# PAYL0001_GMSK.net
KiCad netlist of a schematic drawn in Altium Designer
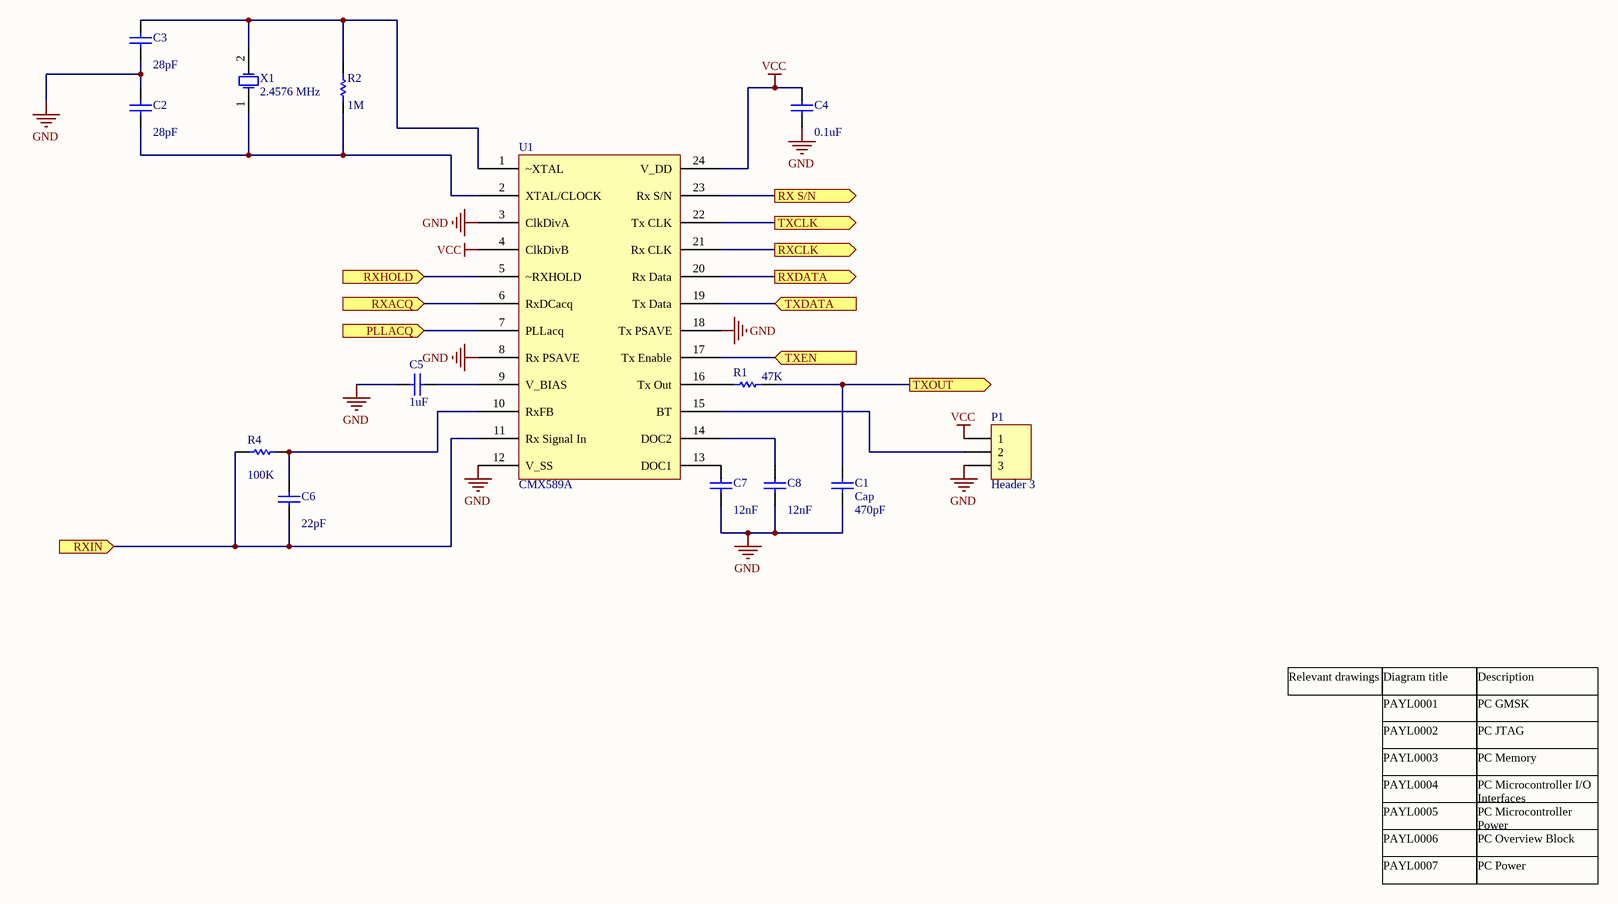
[diagram p0: PAYL0001_GMSK.SchDoc]

(export (version "E")
  (design (tool "Eeschema 10.0.6"))
  (components
    (comp (ref "C1")
      (value "Cap")
      (footprint "C0805")
      (description "Capacitor")
      (fields (field (name "ALTIUM_VALUE") "470pF") (field (name "PUBLISHER") "Altium Limited"))
      (libsource (lib "Miscellaneous Devices") (part "Cap"))
    )
    (comp (ref "C2")
      (value "28pF")
      (footprint "C0805")
      (description "Capacitor")
      (fields (field (name "Comment") "Cap") (field (name "PUBLISHER") "Altium Limited"))
      (libsource (lib "Miscellaneous Devices") (part "Cap"))
    )
    (comp (ref "C3")
      (value "28pF")
      (footprint "C0805")
      (description "Capacitor")
      (fields (field (name "Comment") "Cap") (field (name "PUBLISHER") "Altium Limited"))
      (libsource (lib "Miscellaneous Devices") (part "Cap"))
    )
    (comp (ref "C4")
      (value "0.1uF")
      (footprint "C0805")
      (description "Capacitor")
      (fields (field (name "Comment") "Cap") (field (name "PUBLISHER") "Altium Limited"))
      (libsource (lib "Miscellaneous Devices") (part "Cap"))
    )
    (comp (ref "C5")
      (value "1uF")
      (footprint "C0805")
      (description "Capacitor")
      (fields (field (name "Comment") "Cap") (field (name "PUBLISHER") "Altium Limited"))
      (libsource (lib "Miscellaneous Devices") (part "Cap"))
    )
    (comp (ref "C6")
      (value "22pF")
      (footprint "C0805")
      (description "Capacitor")
      (fields (field (name "Comment") "Cap") (field (name "PUBLISHER") "Altium Limited"))
      (libsource (lib "Miscellaneous Devices") (part "Cap"))
    )
    (comp (ref "C7")
      (value "12nF")
      (footprint "C0805")
      (description "Capacitor")
      (fields (field (name "Comment") "Cap") (field (name "PUBLISHER") "Altium Limited"))
      (libsource (lib "Miscellaneous Devices") (part "Cap"))
    )
    (comp (ref "C8")
      (value "12nF")
      (footprint "C0805")
      (description "Capacitor")
      (fields (field (name "Comment") "Cap") (field (name "PUBLISHER") "Altium Limited"))
      (libsource (lib "Miscellaneous Devices") (part "Cap"))
    )
    (comp (ref "P1")
      (value "Header 3")
      (footprint "HDR1X3")
      (description "Header, 3-Pin")
      (fields (field (name "PUBLISHER") "Altium Limited"))
      (libsource (lib "Miscellaneous Connectors") (part "Header 3"))
    )
    (comp (ref "R1")
      (value "47K")
      (footprint "C0805")
      (description "Resistor")
      (fields (field (name "Comment") "Res1") (field (name "PUBLISHER") "Altium Limited"))
      (libsource (lib "Miscellaneous Devices") (part "Res1"))
    )
    (comp (ref "R2")
      (value "1M")
      (footprint "C0805")
      (description "Resistor")
      (fields (field (name "Comment") "Res1") (field (name "PUBLISHER") "Altium Limited"))
      (libsource (lib "Miscellaneous Devices") (part "Res1"))
    )
    (comp (ref "R4")
      (value "100K")
      (footprint "C0805")
      (description "Resistor")
      (fields (field (name "Comment") "Res1") (field (name "PUBLISHER") "Altium Limited"))
      (libsource (lib "Miscellaneous Devices") (part "Res1"))
    )
    (comp (ref "U1") (value "CMX589A") (footprint "CMX589AD2") (libsource (lib "CMX589A") (part "CMX589A")))
    (comp (ref "X1")
      (value "2.4576 MHz")
      (footprint "XTAL")
      (description "Crystal Oscillator")
      (fields (field (name "PUBLISHER") "Altium Limited"))
      (libsource (lib "Miscellaneous Devices") (part "XTAL"))
    )
  )
  (nets
    (net (code "1") (name "/PLLACQ") (class "Default")
      (node (ref "U1") (pin "7") (pinfunction "PLLacq_7") (pintype "passive"))
    )
    (net (code "2") (name "/RX S{slash}N") (class "Default")
      (node (ref "U1") (pin "23") (pinfunction "Rx_S/N_23") (pintype "passive"))
    )
    (net (code "3") (name "/RXACQ") (class "Default")
      (node (ref "U1") (pin "6") (pinfunction "RxDCacq_6") (pintype "passive"))
    )
    (net (code "4") (name "/RXCLK") (class "Default")
      (node (ref "U1") (pin "21") (pinfunction "Rx_CLK_21") (pintype "passive"))
    )
    (net (code "5") (name "/RXDATA") (class "Default")
      (node (ref "U1") (pin "20") (pinfunction "Rx_Data_20") (pintype "passive"))
    )
    (net (code "6") (name "/RXHOLD") (class "Default")
      (node (ref "U1") (pin "5") (pinfunction "~RXHOLD_5") (pintype "passive"))
    )
    (net (code "7") (name "/RXIN") (class "Default")
      (node (ref "C6") (pin "1") (pinfunction "1_1") (pintype "passive"))
      (node (ref "R4") (pin "1") (pinfunction "1_1") (pintype "passive"))
      (node (ref "U1") (pin "11") (pinfunction "Rx_Signal_In_11") (pintype "passive"))
    )
    (net (code "8") (name "/TXCLK") (class "Default")
      (node (ref "U1") (pin "22") (pinfunction "Tx_CLK_22") (pintype "passive"))
    )
    (net (code "9") (name "/TXDATA") (class "Default")
      (node (ref "U1") (pin "19") (pinfunction "Tx_Data_19") (pintype "passive"))
    )
    (net (code "10") (name "/TXEN") (class "Default")
      (node (ref "U1") (pin "17") (pinfunction "Tx_Enable_17") (pintype "passive"))
    )
    (net (code "11") (name "/TXOUT") (class "Default")
      (node (ref "C1") (pin "2") (pinfunction "2_2") (pintype "passive"))
      (node (ref "R1") (pin "2") (pinfunction "2_2") (pintype "passive"))
    )
    (net (code "12") (name "GND") (class "Default")
      (node (ref "C1") (pin "1") (pinfunction "1_1") (pintype "passive"))
      (node (ref "C2") (pin "2") (pinfunction "2_2") (pintype "passive"))
      (node (ref "C3") (pin "1") (pinfunction "1_1") (pintype "passive"))
      (node (ref "C4") (pin "1") (pinfunction "1_1") (pintype "passive"))
      (node (ref "C5") (pin "1") (pinfunction "1_1") (pintype "passive"))
      (node (ref "C7") (pin "2") (pinfunction "2_2") (pintype "passive"))
      (node (ref "C8") (pin "2") (pinfunction "2_2") (pintype "passive"))
      (node (ref "P1") (pin "3") (pinfunction "3_3") (pintype "passive"))
      (node (ref "U1") (pin "12") (pinfunction "V_SS_12") (pintype "passive"))
      (node (ref "U1") (pin "18") (pinfunction "Tx_PSAVE_18") (pintype "passive"))
      (node (ref "U1") (pin "3") (pinfunction "ClkDivA_3") (pintype "passive"))
      (node (ref "U1") (pin "8") (pinfunction "Rx_PSAVE_8") (pintype "passive"))
    )
    (net (code "13") (name "Net-(U1-BT)") (class "Default")
      (node (ref "P1") (pin "2") (pinfunction "2_2") (pintype "passive"))
      (node (ref "U1") (pin "15") (pinfunction "BT_15") (pintype "passive"))
    )
    (net (code "14") (name "Net-(U1-DOC1)") (class "Default")
      (node (ref "C7") (pin "1") (pinfunction "1_1") (pintype "passive"))
      (node (ref "U1") (pin "13") (pinfunction "DOC1_13") (pintype "passive"))
    )
    (net (code "15") (name "Net-(U1-DOC2)") (class "Default")
      (node (ref "C8") (pin "1") (pinfunction "1_1") (pintype "passive"))
      (node (ref "U1") (pin "14") (pinfunction "DOC2_14") (pintype "passive"))
    )
    (net (code "16") (name "Net-(U1-RxFB)") (class "Default")
      (node (ref "C6") (pin "2") (pinfunction "2_2") (pintype "passive"))
      (node (ref "R4") (pin "2") (pinfunction "2_2") (pintype "passive"))
      (node (ref "U1") (pin "10") (pinfunction "RxFB_10") (pintype "passive"))
    )
    (net (code "17") (name "Net-(U1-Tx_Out)") (class "Default")
      (node (ref "R1") (pin "1") (pinfunction "1_1") (pintype "passive"))
      (node (ref "U1") (pin "16") (pinfunction "Tx_Out_16") (pintype "passive"))
    )
    (net (code "18") (name "Net-(U1-V_BIAS)") (class "Default")
      (node (ref "C5") (pin "2") (pinfunction "2_2") (pintype "passive"))
      (node (ref "U1") (pin "9") (pinfunction "V_BIAS_9") (pintype "passive"))
    )
    (net (code "19") (name "Net-(U1-XTAL{slash}CLOCK)") (class "Default")
      (node (ref "C2") (pin "1") (pinfunction "1_1") (pintype "passive"))
      (node (ref "R2") (pin "1") (pinfunction "1_1") (pintype "passive"))
      (node (ref "U1") (pin "2") (pinfunction "XTAL/CLOCK_2") (pintype "passive"))
      (node (ref "X1") (pin "1") (pinfunction "OSC1_1") (pintype "passive"))
    )
    (net (code "20") (name "Net-(U1-~XTAL)") (class "Default")
      (node (ref "C3") (pin "2") (pinfunction "2_2") (pintype "passive"))
      (node (ref "R2") (pin "2") (pinfunction "2_2") (pintype "passive"))
      (node (ref "U1") (pin "1") (pinfunction "~XTAL_1") (pintype "passive"))
      (node (ref "X1") (pin "2") (pinfunction "OSC2_2") (pintype "passive"))
    )
    (net (code "21") (name "VCC") (class "Default")
      (node (ref "C4") (pin "2") (pinfunction "2_2") (pintype "passive"))
      (node (ref "P1") (pin "1") (pinfunction "1_1") (pintype "passive"))
      (node (ref "U1") (pin "24") (pinfunction "V_DD_24") (pintype "passive"))
      (node (ref "U1") (pin "4") (pinfunction "ClkDivB_4") (pintype "passive"))
    )
  )
)
